# Connectors.net
KiCad netlist of a schematic drawn in Altium Designer
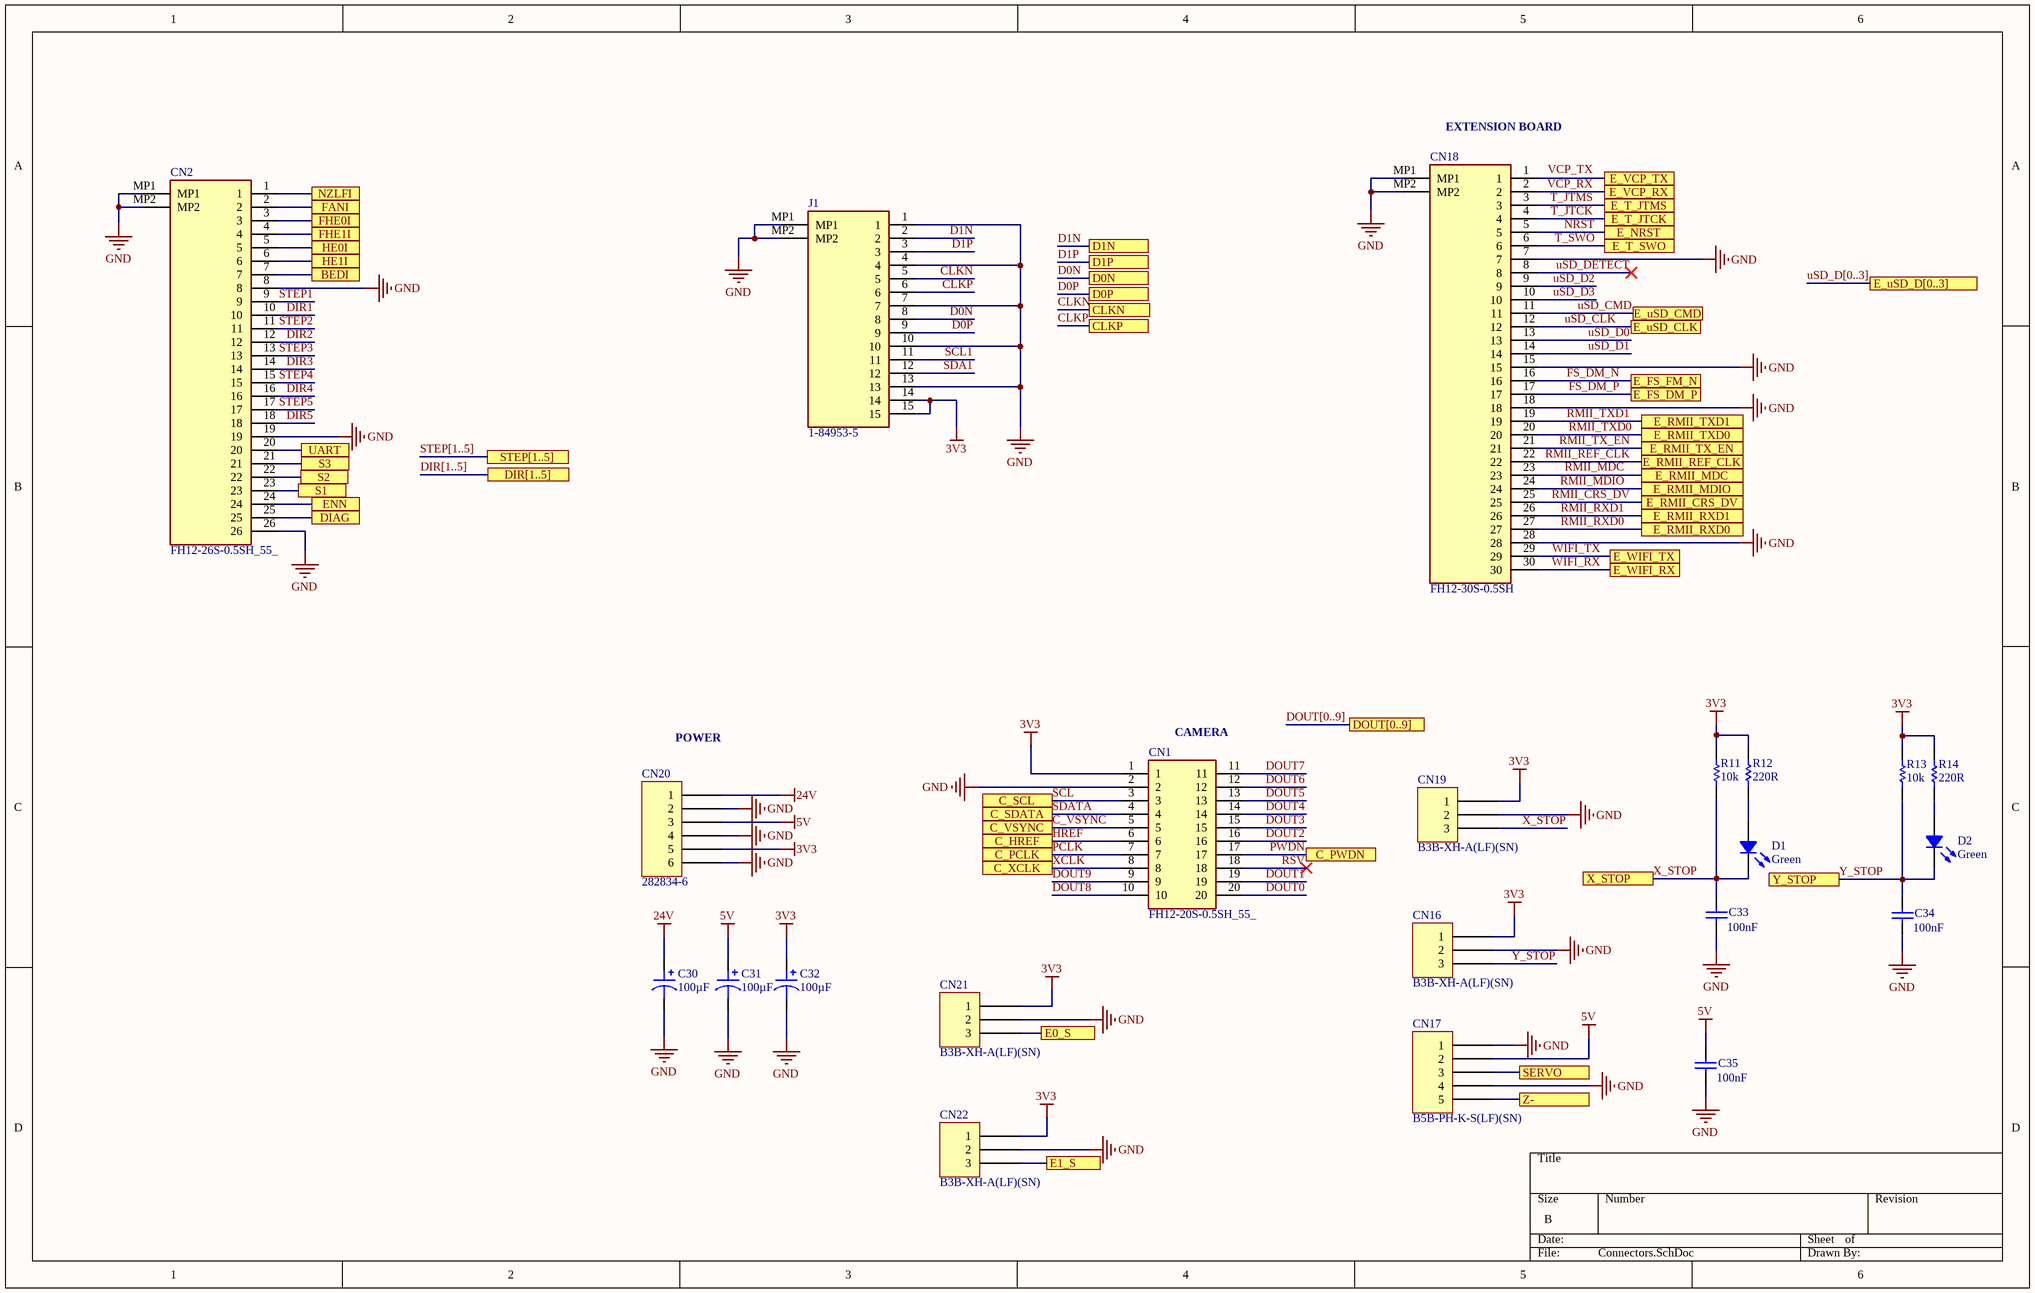
[diagram p0: Connectors.SchDoc]

(export (version "E")
  (design (tool "Eeschema 10.0.6"))
  (components
    (comp (ref "C30")
      (value "100µF")
      (footprint "CAP ALSMD POLY 5.3MM H6.0MM")
      (description "CAP ALUM POLY 100UF 20% 6.3V SMD")
      (fields
        (field (name "PART NUMBER") "6SVPC100M")
        (field (name "MANUFACTURER") "Panasonic Electronic Components")
      )
      (libsource (lib "Celestial Altium Library - altium_library") (part "Polarised Capacitor"))
    )
    (comp (ref "C31")
      (value "100µF")
      (footprint "CAP ALSMD POLY 5.3MM H6.0MM")
      (description "CAP ALUM POLY 100UF 20% 6.3V SMD")
      (fields
        (field (name "PART NUMBER") "6SVPC100M")
        (field (name "MANUFACTURER") "Panasonic Electronic Components")
      )
      (libsource (lib "Celestial Altium Library - altium_library") (part "Polarised Capacitor"))
    )
    (comp (ref "C32")
      (value "100µF")
      (footprint "CAP ALSMD POLY 5.3MM H6.0MM")
      (description "CAP ALUM POLY 100UF 20% 6.3V SMD")
      (fields
        (field (name "PART NUMBER") "6SVPC100M")
        (field (name "MANUFACTURER") "Panasonic Electronic Components")
      )
      (libsource (lib "Celestial Altium Library - altium_library") (part "Polarised Capacitor"))
    )
    (comp (ref "C33")
      (value "100nF")
      (footprint "1608[0603]")
      (description "Capacitor")
      (fields (field (name "Comment") "X5R") (field (name "PUBLISHER") "Altium Limited"))
      (libsource (lib "Miscellaneous Devices") (part "Cap"))
    )
    (comp (ref "C34")
      (value "100nF")
      (footprint "1608[0603]")
      (description "Capacitor")
      (fields (field (name "Comment") "X5R") (field (name "PUBLISHER") "Altium Limited"))
      (libsource (lib "Miscellaneous Devices") (part "Cap"))
    )
    (comp (ref "C35")
      (value "100nF")
      (footprint "1608[0603]")
      (description "Capacitor")
      (fields (field (name "Comment") "X5R") (field (name "PUBLISHER") "Altium Limited"))
      (libsource (lib "Miscellaneous Devices") (part "Cap"))
    )
    (comp (ref "CN1")
      (value "FH12-20S-0.5SH_55_")
      (footprint "SamacSys:FH12-20S-0.5SH(55)")
      (description "Connector")
      (fields
        (field (name "MANUFACTURER_PART_NUMBER") "FH12-20S-0.5SH(55)")
        (field (name "MOUSER PART NUMBER") "798-FH12-20S-0.5SH55")
      )
      (libsource (lib "*") (part "FH12-20S-0.5SH_55_"))
    )
    (comp (ref "CN2")
      (value "FH12-26S-0.5SH_55_")
      (footprint "SamacSys:FH1226S05SH55")
      (description "Connector")
      (fields
        (field (name "MANUFACTURER_PART_NUMBER") "FH12-26S-0.5SH(55)")
        (field (name "MOUSER PART NUMBER") "798-FH12-26S-0.5SH55")
      )
      (libsource (lib "SamacSys") (part "FH12-26S-0.5SH_55_"))
    )
    (comp (ref "CN16")
      (value "B3B-XH-A(LF)(SN)")
      (footprint "JST XH B3B-XH-A")
      (description "CONN HEADER VERT 3POS 2.5MM")
      (fields (field (name "MANUFACTURER") "JST Sales America Inc."))
      (libsource (lib "Celestial Altium Library - altium_library") (part "3 Pin"))
    )
    (comp (ref "CN17")
      (value "B5B-PH-K-S(LF)(SN)")
      (footprint "JST B5B-PH-K")
      (description "CONN HEADER VERT 5POS 2MM")
      (fields (field (name "MANUFACTURER") "JST Sales America Inc."))
      (libsource (lib "Celestial Altium Library - altium_library") (part "5 Pin"))
    )
    (comp (ref "CN18")
      (value "FH12-30S-0.5SH")
      (footprint "SamacSys:FH1230S05SH")
      (description "Connector")
      (libsource (lib "*") (part "FH12-30S-0.5SH"))
    )
    (comp (ref "CN19")
      (value "B3B-XH-A(LF)(SN)")
      (footprint "JST XH B3B-XH-A")
      (description "CONN HEADER VERT 3POS 2.5MM")
      (fields (field (name "MANUFACTURER") "JST Sales America Inc."))
      (libsource (lib "Celestial Altium Library - altium_library") (part "3 Pin"))
    )
    (comp (ref "CN20")
      (value "282834-6")
      (footprint "TE 282834-6")
      (description "TERM BLK 6P SIDE ENT 2.54MM PCB")
      (fields (field (name "MANUFACTURER") "TE Connectivity AMP Connectors") (field (name "VOLTAGE") "150V"))
      (libsource (lib "Celestial Altium Library - altium_library") (part "6 Pin"))
    )
    (comp (ref "CN21")
      (value "B3B-XH-A(LF)(SN)")
      (footprint "JST XH B3B-XH-A")
      (description "CONN HEADER VERT 3POS 2.5MM")
      (fields (field (name "MANUFACTURER") "JST Sales America Inc."))
      (libsource (lib "Celestial Altium Library - altium_library") (part "3 Pin"))
    )
    (comp (ref "CN22")
      (value "B3B-XH-A(LF)(SN)")
      (footprint "JST XH B3B-XH-A")
      (description "CONN HEADER VERT 3POS 2.5MM")
      (fields (field (name "MANUFACTURER") "JST Sales America Inc."))
      (libsource (lib "Celestial Altium Library - altium_library") (part "3 Pin"))
    )
    (comp (ref "D1")
      (value "Green")
      (footprint "LED 0805_2012 GREEN")
      (description "LED GREEN CLEAR 0805 SMD")
      (fields
        (field (name "PART NUMBER") "QTLP630C4TR")
        (field (name "MANUFACTURER") "Everlight Electronics Co Ltd")
      )
      (libsource (lib "Celestial Altium Library - altium_library") (part "LED"))
    )
    (comp (ref "D2")
      (value "Green")
      (footprint "LED 0805_2012 GREEN")
      (description "LED GREEN CLEAR 0805 SMD")
      (fields
        (field (name "PART NUMBER") "QTLP630C4TR")
        (field (name "MANUFACTURER") "Everlight Electronics Co Ltd")
      )
      (libsource (lib "Celestial Altium Library - altium_library") (part "LED"))
    )
    (comp (ref "J1")
      (value "1-84953-5")
      (footprint "SamacSys:1849535")
      (description "Connector")
      (fields (field (name "MOUSER PART NUMBER") "571-1-84953-5"))
      (libsource (lib "*") (part "1-84953-5"))
    )
    (comp (ref "R11")
      (value "10k")
      (footprint "1608[0603]")
      (description "Resistor")
      (fields (field (name "Comment") "Res1") (field (name "PUBLISHER") "Altium Limited"))
      (libsource (lib "Miscellaneous Devices") (part "Res1"))
    )
    (comp (ref "R12")
      (value "220R")
      (footprint "1608[0603]")
      (description "Resistor")
      (fields (field (name "Comment") "Res1") (field (name "PUBLISHER") "Altium Limited"))
      (libsource (lib "Miscellaneous Devices") (part "Res1"))
    )
    (comp (ref "R13")
      (value "10k")
      (footprint "1608[0603]")
      (description "Resistor")
      (fields (field (name "Comment") "Res1") (field (name "PUBLISHER") "Altium Limited"))
      (libsource (lib "Miscellaneous Devices") (part "Res1"))
    )
    (comp (ref "R14")
      (value "220R")
      (footprint "1608[0603]")
      (description "Resistor")
      (fields (field (name "Comment") "Res1") (field (name "PUBLISHER") "Altium Limited"))
      (libsource (lib "Miscellaneous Devices") (part "Res1"))
    )
  )
  (nets
    (net (code "1") (name "/BEDI") (class "Default")
      (node (ref "CN2") (pin "7") (pinfunction "7_7") (pintype "passive"))
    )
    (net (code "2") (name "/CLKN") (class "Default")
      (node (ref "J1") (pin "5") (pinfunction "5_5") (pintype "passive"))
    )
    (net (code "3") (name "/CLKP") (class "Default")
      (node (ref "J1") (pin "6") (pinfunction "6_6") (pintype "passive"))
    )
    (net (code "4") (name "/C_VSYNC") (class "Default")
      (node (ref "CN1") (pin "5") (pinfunction "5_5") (pintype "passive"))
    )
    (net (code "5") (name "/D0N") (class "Default")
      (node (ref "J1") (pin "8") (pinfunction "8_8") (pintype "passive"))
    )
    (net (code "6") (name "/D0P") (class "Default")
      (node (ref "J1") (pin "9") (pinfunction "9_9") (pintype "passive"))
    )
    (net (code "7") (name "/D1N") (class "Default")
      (node (ref "J1") (pin "2") (pinfunction "2_2") (pintype "passive"))
    )
    (net (code "8") (name "/D1P") (class "Default")
      (node (ref "J1") (pin "3") (pinfunction "3_3") (pintype "passive"))
    )
    (net (code "9") (name "/DIAG") (class "Default")
      (node (ref "CN2") (pin "25") (pinfunction "25_25") (pintype "passive"))
    )
    (net (code "10") (name "/DIR1") (class "Default")
      (node (ref "CN2") (pin "10") (pinfunction "10_10") (pintype "passive"))
    )
    (net (code "11") (name "/DIR2") (class "Default")
      (node (ref "CN2") (pin "12") (pinfunction "12_12") (pintype "passive"))
    )
    (net (code "12") (name "/DIR3") (class "Default")
      (node (ref "CN2") (pin "14") (pinfunction "14_14") (pintype "passive"))
    )
    (net (code "13") (name "/DIR4") (class "Default")
      (node (ref "CN2") (pin "16") (pinfunction "16_16") (pintype "passive"))
    )
    (net (code "14") (name "/DIR5") (class "Default")
      (node (ref "CN2") (pin "18") (pinfunction "18_18") (pintype "passive"))
    )
    (net (code "16") (name "/DOUT0") (class "Default")
      (node (ref "CN1") (pin "20") (pinfunction "20_20") (pintype "passive"))
    )
    (net (code "17") (name "/DOUT1") (class "Default")
      (node (ref "CN1") (pin "19") (pinfunction "19_19") (pintype "passive"))
    )
    (net (code "18") (name "/DOUT2") (class "Default")
      (node (ref "CN1") (pin "16") (pinfunction "16_16") (pintype "passive"))
    )
    (net (code "19") (name "/DOUT3") (class "Default")
      (node (ref "CN1") (pin "15") (pinfunction "15_15") (pintype "passive"))
    )
    (net (code "20") (name "/DOUT4") (class "Default")
      (node (ref "CN1") (pin "14") (pinfunction "14_14") (pintype "passive"))
    )
    (net (code "21") (name "/DOUT5") (class "Default")
      (node (ref "CN1") (pin "13") (pinfunction "13_13") (pintype "passive"))
    )
    (net (code "22") (name "/DOUT6") (class "Default")
      (node (ref "CN1") (pin "12") (pinfunction "12_12") (pintype "passive"))
    )
    (net (code "23") (name "/DOUT7") (class "Default")
      (node (ref "CN1") (pin "11") (pinfunction "11_11") (pintype "passive"))
    )
    (net (code "24") (name "/DOUT8") (class "Default")
      (node (ref "CN1") (pin "10") (pinfunction "10_10") (pintype "passive"))
    )
    (net (code "25") (name "/DOUT9") (class "Default")
      (node (ref "CN1") (pin "9") (pinfunction "9_9") (pintype "passive"))
    )
    (net (code "27") (name "/E0_S") (class "Default")
      (node (ref "CN21") (pin "3") (pinfunction "3_3") (pintype "passive"))
    )
    (net (code "28") (name "/E1_S") (class "Default")
      (node (ref "CN22") (pin "3") (pinfunction "3_3") (pintype "passive"))
    )
    (net (code "29") (name "/ENN") (class "Default")
      (node (ref "CN2") (pin "24") (pinfunction "24_24") (pintype "passive"))
    )
    (net (code "30") (name "/E_RMII_MDC") (class "Default")
      (node (ref "CN18") (pin "23") (pinfunction "23_23") (pintype "passive"))
    )
    (net (code "31") (name "/E_VCP_TX") (class "Default")
      (node (ref "CN18") (pin "1") (pinfunction "1_1") (pintype "passive"))
    )
    (net (code "32") (name "/FANI") (class "Default")
      (node (ref "CN2") (pin "2") (pinfunction "2_2") (pintype "passive"))
    )
    (net (code "33") (name "/FHE0I") (class "Default")
      (node (ref "CN2") (pin "3") (pinfunction "3_3") (pintype "passive"))
    )
    (net (code "34") (name "/FHE1I") (class "Default")
      (node (ref "CN2") (pin "4") (pinfunction "4_4") (pintype "passive"))
    )
    (net (code "35") (name "/FS_DM_N") (class "Default")
      (node (ref "CN18") (pin "16") (pinfunction "16_16") (pintype "passive"))
    )
    (net (code "36") (name "/FS_DM_P") (class "Default")
      (node (ref "CN18") (pin "17") (pinfunction "17_17") (pintype "passive"))
    )
    (net (code "37") (name "/HE0I") (class "Default")
      (node (ref "CN2") (pin "5") (pinfunction "5_5") (pintype "passive"))
    )
    (net (code "38") (name "/HE1I") (class "Default")
      (node (ref "CN2") (pin "6") (pinfunction "6_6") (pintype "passive"))
    )
    (net (code "39") (name "/HREF") (class "Default")
      (node (ref "CN1") (pin "6") (pinfunction "6_6") (pintype "passive"))
    )
    (net (code "40") (name "/NRST") (class "Default")
      (node (ref "CN18") (pin "5") (pinfunction "5_5") (pintype "passive"))
    )
    (net (code "41") (name "/NZLFI") (class "Default")
      (node (ref "CN2") (pin "1") (pinfunction "1_1") (pintype "passive"))
    )
    (net (code "42") (name "/PCLK") (class "Default")
      (node (ref "CN1") (pin "7") (pinfunction "7_7") (pintype "passive"))
    )
    (net (code "43") (name "/PWDN") (class "Default")
      (node (ref "CN1") (pin "17") (pinfunction "17_17") (pintype "passive"))
    )
    (net (code "44") (name "/RMII_CRS_DV") (class "Default")
      (node (ref "CN18") (pin "25") (pinfunction "25_25") (pintype "passive"))
    )
    (net (code "46") (name "/RMII_MDIO") (class "Default")
      (node (ref "CN18") (pin "24") (pinfunction "24_24") (pintype "passive"))
    )
    (net (code "47") (name "/RMII_REF_CLK") (class "Default")
      (node (ref "CN18") (pin "22") (pinfunction "22_22") (pintype "passive"))
    )
    (net (code "48") (name "/RMII_RXD0") (class "Default")
      (node (ref "CN18") (pin "27") (pinfunction "27_27") (pintype "passive"))
    )
    (net (code "49") (name "/RMII_RXD1") (class "Default")
      (node (ref "CN18") (pin "26") (pinfunction "26_26") (pintype "passive"))
    )
    (net (code "50") (name "/RMII_TXD0") (class "Default")
      (node (ref "CN18") (pin "20") (pinfunction "20_20") (pintype "passive"))
    )
    (net (code "51") (name "/RMII_TXD1") (class "Default")
      (node (ref "CN18") (pin "19") (pinfunction "19_19") (pintype "passive"))
    )
    (net (code "52") (name "/RMII_TX_EN") (class "Default")
      (node (ref "CN18") (pin "21") (pinfunction "21_21") (pintype "passive"))
    )
    (net (code "53") (name "/RSV") (class "Default")
      (node (ref "CN1") (pin "18") (pinfunction "18_18") (pintype "passive+no_connect"))
    )
    (net (code "54") (name "/S1") (class "Default")
      (node (ref "CN2") (pin "23") (pinfunction "23_23") (pintype "passive"))
    )
    (net (code "55") (name "/S2") (class "Default")
      (node (ref "CN2") (pin "22") (pinfunction "22_22") (pintype "passive"))
    )
    (net (code "56") (name "/S3") (class "Default")
      (node (ref "CN2") (pin "21") (pinfunction "21_21") (pintype "passive"))
    )
    (net (code "57") (name "/SCL") (class "Default")
      (node (ref "CN1") (pin "3") (pinfunction "3_3") (pintype "passive"))
    )
    (net (code "58") (name "/SCL1") (class "Default")
      (node (ref "J1") (pin "11") (pinfunction "11_11") (pintype "passive"))
    )
    (net (code "59") (name "/SDA1") (class "Default")
      (node (ref "J1") (pin "12") (pinfunction "12_12") (pintype "passive"))
    )
    (net (code "60") (name "/SDATA") (class "Default")
      (node (ref "CN1") (pin "4") (pinfunction "4_4") (pintype "passive"))
    )
    (net (code "61") (name "/SERVO") (class "Default")
      (node (ref "CN17") (pin "3") (pinfunction "3_3") (pintype "passive"))
    )
    (net (code "62") (name "/STEP1") (class "Default")
      (node (ref "CN2") (pin "9") (pinfunction "9_9") (pintype "passive"))
    )
    (net (code "63") (name "/STEP2") (class "Default")
      (node (ref "CN2") (pin "11") (pinfunction "11_11") (pintype "passive"))
    )
    (net (code "64") (name "/STEP3") (class "Default")
      (node (ref "CN2") (pin "13") (pinfunction "13_13") (pintype "passive"))
    )
    (net (code "65") (name "/STEP4") (class "Default")
      (node (ref "CN2") (pin "15") (pinfunction "15_15") (pintype "passive"))
    )
    (net (code "66") (name "/STEP5") (class "Default")
      (node (ref "CN2") (pin "17") (pinfunction "17_17") (pintype "passive"))
    )
    (net (code "68") (name "/T_JTCK") (class "Default")
      (node (ref "CN18") (pin "4") (pinfunction "4_4") (pintype "passive"))
    )
    (net (code "69") (name "/T_JTMS") (class "Default")
      (node (ref "CN18") (pin "3") (pinfunction "3_3") (pintype "passive"))
    )
    (net (code "70") (name "/T_SWO") (class "Default")
      (node (ref "CN18") (pin "6") (pinfunction "6_6") (pintype "passive"))
    )
    (net (code "71") (name "/UART") (class "Default")
      (node (ref "CN2") (pin "20") (pinfunction "20_20") (pintype "passive"))
    )
    (net (code "72") (name "/VCP_RX") (class "Default")
      (node (ref "CN18") (pin "2") (pinfunction "2_2") (pintype "passive"))
    )
    (net (code "74") (name "/WIFI_RX") (class "Default")
      (node (ref "CN18") (pin "30") (pinfunction "30_30") (pintype "passive"))
    )
    (net (code "75") (name "/WIFI_TX") (class "Default")
      (node (ref "CN18") (pin "29") (pinfunction "29_29") (pintype "passive"))
    )
    (net (code "76") (name "/XCLK") (class "Default")
      (node (ref "CN1") (pin "8") (pinfunction "8_8") (pintype "passive"))
    )
    (net (code "77") (name "/X_STOP") (class "Default")
      (node (ref "C33") (pin "1") (pinfunction "1_1") (pintype "passive"))
      (node (ref "CN19") (pin "3") (pinfunction "3_3") (pintype "passive"))
      (node (ref "D1") (pin "2") (pinfunction "2_2") (pintype "passive"))
      (node (ref "R11") (pin "2") (pinfunction "2_2") (pintype "passive"))
    )
    (net (code "78") (name "/Y_STOP") (class "Default")
      (node (ref "C34") (pin "1") (pinfunction "1_1") (pintype "passive"))
      (node (ref "CN16") (pin "3") (pinfunction "3_3") (pintype "passive"))
      (node (ref "D2") (pin "2") (pinfunction "2_2") (pintype "passive"))
      (node (ref "R13") (pin "2") (pinfunction "2_2") (pintype "passive"))
    )
    (net (code "79") (name "/Z-") (class "Default")
      (node (ref "CN17") (pin "5") (pinfunction "5_5") (pintype "passive"))
    )
    (net (code "80") (name "/uSD_CLK") (class "Default")
      (node (ref "CN18") (pin "12") (pinfunction "12_12") (pintype "passive"))
    )
    (net (code "81") (name "/uSD_CMD") (class "Default")
      (node (ref "CN18") (pin "11") (pinfunction "11_11") (pintype "passive"))
    )
    (net (code "82") (name "/uSD_D0") (class "Default")
      (node (ref "CN18") (pin "13") (pinfunction "13_13") (pintype "passive"))
    )
    (net (code "83") (name "/uSD_D1") (class "Default")
      (node (ref "CN18") (pin "14") (pinfunction "14_14") (pintype "passive"))
    )
    (net (code "84") (name "/uSD_D2") (class "Default")
      (node (ref "CN18") (pin "9") (pinfunction "9_9") (pintype "passive"))
    )
    (net (code "85") (name "/uSD_D3") (class "Default")
      (node (ref "CN18") (pin "10") (pinfunction "10_10") (pintype "passive"))
    )
    (net (code "86") (name "/uSD_DETECT") (class "Default")
      (node (ref "CN18") (pin "8") (pinfunction "8_8") (pintype "passive+no_connect"))
    )
    (net (code "88") (name "3V3") (class "Default")
      (node (ref "C32") (pin "1") (pinfunction "1_1") (pintype "passive"))
      (node (ref "CN1") (pin "1") (pinfunction "1_1") (pintype "passive"))
      (node (ref "CN16") (pin "1") (pinfunction "1_1") (pintype "passive"))
      (node (ref "CN19") (pin "1") (pinfunction "1_1") (pintype "passive"))
      (node (ref "CN20") (pin "5") (pinfunction "5_5") (pintype "passive"))
      (node (ref "CN21") (pin "1") (pinfunction "1_1") (pintype "passive"))
      (node (ref "CN22") (pin "1") (pinfunction "1_1") (pintype "passive"))
      (node (ref "J1") (pin "14") (pinfunction "14_14") (pintype "passive"))
      (node (ref "J1") (pin "15") (pinfunction "15_15") (pintype "passive"))
      (node (ref "R11") (pin "1") (pinfunction "1_1") (pintype "passive"))
      (node (ref "R12") (pin "1") (pinfunction "1_1") (pintype "passive"))
      (node (ref "R13") (pin "1") (pinfunction "1_1") (pintype "passive"))
      (node (ref "R14") (pin "1") (pinfunction "1_1") (pintype "passive"))
    )
    (net (code "89") (name "5V") (class "Default")
      (node (ref "C31") (pin "1") (pinfunction "1_1") (pintype "passive"))
      (node (ref "C35") (pin "1") (pinfunction "1_1") (pintype "passive"))
      (node (ref "CN17") (pin "2") (pinfunction "2_2") (pintype "passive"))
      (node (ref "CN20") (pin "3") (pinfunction "3_3") (pintype "passive"))
    )
    (net (code "90") (name "24V") (class "Default")
      (node (ref "C30") (pin "1") (pinfunction "1_1") (pintype "passive"))
      (node (ref "CN20") (pin "1") (pinfunction "1_1") (pintype "passive"))
    )
    (net (code "91") (name "GND") (class "Default")
      (node (ref "C30") (pin "2") (pinfunction "2_2") (pintype "passive"))
      (node (ref "C31") (pin "2") (pinfunction "2_2") (pintype "passive"))
      (node (ref "C32") (pin "2") (pinfunction "2_2") (pintype "passive"))
      (node (ref "C33") (pin "2") (pinfunction "2_2") (pintype "passive"))
      (node (ref "C34") (pin "2") (pinfunction "2_2") (pintype "passive"))
      (node (ref "C35") (pin "2") (pinfunction "2_2") (pintype "passive"))
      (node (ref "CN1") (pin "2") (pinfunction "2_2") (pintype "passive"))
      (node (ref "CN16") (pin "2") (pinfunction "2_2") (pintype "passive"))
      (node (ref "CN17") (pin "1") (pinfunction "1_1") (pintype "passive"))
      (node (ref "CN17") (pin "4") (pinfunction "4_4") (pintype "passive"))
      (node (ref "CN18") (pin "15") (pinfunction "15_15") (pintype "passive"))
      (node (ref "CN18") (pin "18") (pinfunction "18_18") (pintype "passive"))
      (node (ref "CN18") (pin "28") (pinfunction "28_28") (pintype "passive"))
      (node (ref "CN18") (pin "7") (pinfunction "7_7") (pintype "passive"))
      (node (ref "CN18") (pin "MP1") (pinfunction "MP1_MP1") (pintype "passive"))
      (node (ref "CN18") (pin "MP2") (pinfunction "MP2_MP2") (pintype "passive"))
      (node (ref "CN19") (pin "2") (pinfunction "2_2") (pintype "passive"))
      (node (ref "CN2") (pin "19") (pinfunction "19_19") (pintype "passive"))
      (node (ref "CN2") (pin "26") (pinfunction "26_26") (pintype "passive"))
      (node (ref "CN2") (pin "8") (pinfunction "8_8") (pintype "passive"))
      (node (ref "CN2") (pin "MP1") (pinfunction "MP1_MP1") (pintype "passive"))
      (node (ref "CN2") (pin "MP2") (pinfunction "MP2_MP2") (pintype "passive"))
      (node (ref "CN20") (pin "2") (pinfunction "2_2") (pintype "passive"))
      (node (ref "CN20") (pin "4") (pinfunction "4_4") (pintype "passive"))
      (node (ref "CN20") (pin "6") (pinfunction "6_6") (pintype "passive"))
      (node (ref "CN21") (pin "2") (pinfunction "2_2") (pintype "passive"))
      (node (ref "CN22") (pin "2") (pinfunction "2_2") (pintype "passive"))
      (node (ref "J1") (pin "1") (pinfunction "1_1") (pintype "passive"))
      (node (ref "J1") (pin "10") (pinfunction "10_10") (pintype "passive"))
      (node (ref "J1") (pin "13") (pinfunction "13_13") (pintype "passive"))
      (node (ref "J1") (pin "4") (pinfunction "4_4") (pintype "passive"))
      (node (ref "J1") (pin "7") (pinfunction "7_7") (pintype "passive"))
      (node (ref "J1") (pin "MP1") (pinfunction "MP1_MP1") (pintype "passive"))
      (node (ref "J1") (pin "MP2") (pinfunction "MP2_MP2") (pintype "passive"))
    )
    (net (code "92") (name "Net-(D1-Pad1)") (class "Default")
      (node (ref "D1") (pin "1") (pinfunction "1_1") (pintype "passive"))
      (node (ref "R12") (pin "2") (pinfunction "2_2") (pintype "passive"))
    )
    (net (code "93") (name "Net-(D2-Pad1)") (class "Default")
      (node (ref "D2") (pin "1") (pinfunction "1_1") (pintype "passive"))
      (node (ref "R14") (pin "2") (pinfunction "2_2") (pintype "passive"))
    )
  )
)
